# Pi_Zero_Radio_Alt_Hat.net
KiCad netlist of a schematic drawn in EasyEDA
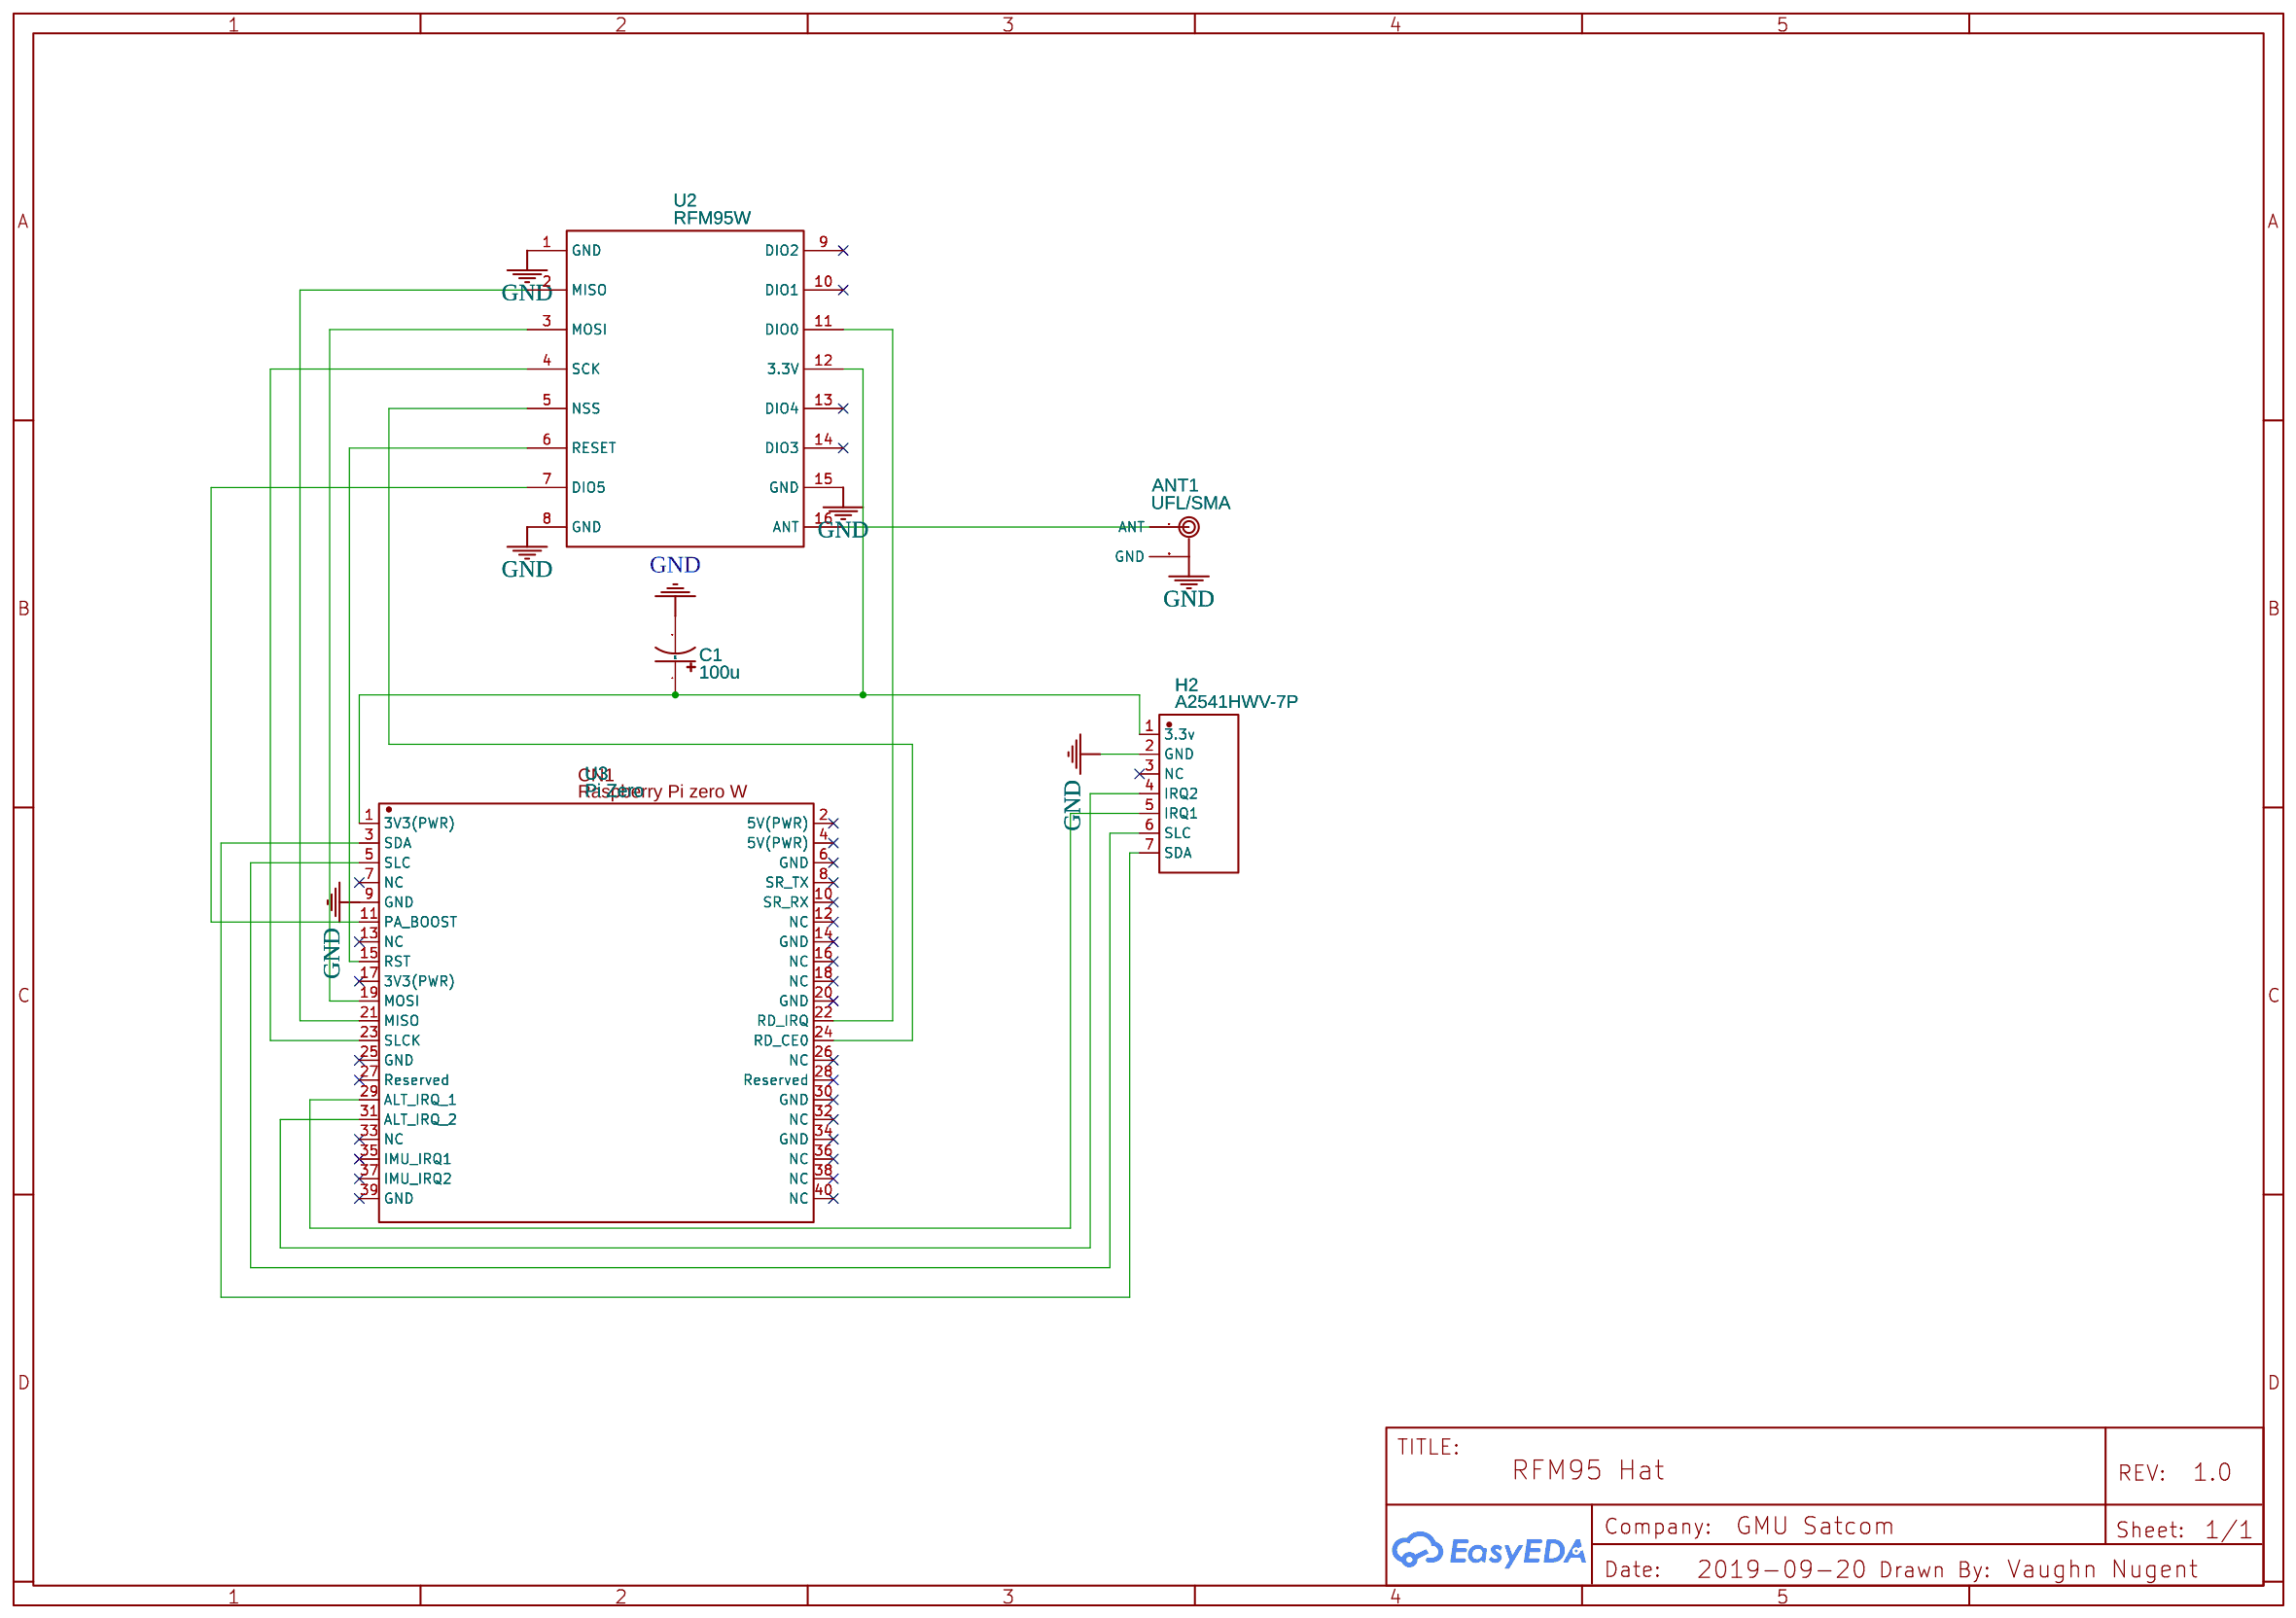
[diagram p0: schematic sheet]

(export (version "E")
  (design (tool "Eeschema 10.0.6"))
  (components
    (comp (ref "ANT1")
      (value "UFL/SMA")
      (fields (field (name "BOM_Manufacturer Part") "UFL/SMA anténa"))
      (libsource (lib "") (part "Unknown_595_275"))
    )
    (comp (ref "C1") (value "100u") (libsource (lib "") (part "Cap_Electrolytic(TH)_D3.0XF1.5_US")))
    (comp (ref "H2")
      (value "A2541HWV-7P")
      (fields (field (name "BOM_Supplier Part") "C225504"))
      (libsource (lib "") (part "Unknown_595_395"))
    )
    (comp (ref "U2") (value "RFM95W") (libsource (lib "") (part "Unknown_340_190")))
    (comp (ref "U3") (value "Pi Zero") (libsource (lib "") (part "Unknown_295_495")))
  )
  (nets
    (net (code "1") (name "GND") (class "Default")
      (node (ref "ANT1") (pin "GND") (pinfunction "GND_GND") (pintype "unspecified"))
      (node (ref "C1") (pin "2") (pinfunction "Neg_2") (pintype "unspecified"))
      (node (ref "H2") (pin "2") (pinfunction "GND_2") (pintype "unspecified"))
      (node (ref "U2") (pin "1") (pinfunction "GND_1") (pintype "unspecified"))
      (node (ref "U2") (pin "15") (pinfunction "GND_15") (pintype "unspecified"))
      (node (ref "U2") (pin "8") (pinfunction "GND_8") (pintype "unspecified"))
      (node (ref "U3") (pin "9") (pinfunction "GND_9") (pintype "passive"))
    )
    (net (code "2") (name "Net-(C1-Pos)") (class "Default")
      (node (ref "C1") (pin "1") (pinfunction "Pos_1") (pintype "unspecified"))
      (node (ref "H2") (pin "1") (pinfunction "3.3v_1") (pintype "unspecified"))
      (node (ref "U2") (pin "12") (pinfunction "3.3V_12") (pintype "unspecified"))
      (node (ref "U3") (pin "1") (pinfunction "3V3(PWR)_1") (pintype "passive"))
    )
    (net (code "3") (name "Net-(H2-IRQ1)") (class "Default")
      (node (ref "H2") (pin "5") (pinfunction "IRQ1_5") (pintype "unspecified"))
      (node (ref "U3") (pin "29") (pinfunction "ALT_IRQ_1_29") (pintype "bidirectional"))
    )
    (net (code "4") (name "Net-(H2-IRQ2)") (class "Default")
      (node (ref "H2") (pin "4") (pinfunction "IRQ2_4") (pintype "unspecified"))
      (node (ref "U3") (pin "31") (pinfunction "ALT_IRQ_2_31") (pintype "bidirectional"))
    )
    (net (code "5") (name "Net-(H2-SDA)") (class "Default")
      (node (ref "H2") (pin "7") (pinfunction "SDA_7") (pintype "unspecified"))
      (node (ref "U3") (pin "3") (pinfunction "SDA_3") (pintype "bidirectional"))
    )
    (net (code "6") (name "Net-(H2-SLC)") (class "Default")
      (node (ref "H2") (pin "6") (pinfunction "SLC_6") (pintype "unspecified"))
      (node (ref "U3") (pin "5") (pinfunction "SLC_5") (pintype "bidirectional"))
    )
    (net (code "7") (name "Net-(U2-ANT)") (class "Default")
      (node (ref "ANT1") (pin "ANT") (pinfunction "ANT_ANT") (pintype "unspecified"))
      (node (ref "U2") (pin "16") (pinfunction "ANT_16") (pintype "unspecified"))
    )
    (net (code "8") (name "Net-(U2-DIO0)") (class "Default")
      (node (ref "U2") (pin "11") (pinfunction "DIO0_11") (pintype "unspecified"))
      (node (ref "U3") (pin "22") (pinfunction "RD_IRQ_22") (pintype "bidirectional"))
    )
    (net (code "9") (name "Net-(U2-DIO5)") (class "Default")
      (node (ref "U2") (pin "7") (pinfunction "DIO5_7") (pintype "unspecified"))
      (node (ref "U3") (pin "11") (pinfunction "PA_BOOST_11") (pintype "bidirectional"))
    )
    (net (code "10") (name "Net-(U2-MISO)") (class "Default")
      (node (ref "U2") (pin "2") (pinfunction "MISO_2") (pintype "unspecified"))
      (node (ref "U3") (pin "21") (pinfunction "MISO_21") (pintype "bidirectional"))
    )
    (net (code "11") (name "Net-(U2-MOSI)") (class "Default")
      (node (ref "U2") (pin "3") (pinfunction "MOSI_3") (pintype "unspecified"))
      (node (ref "U3") (pin "19") (pinfunction "MOSI_19") (pintype "bidirectional"))
    )
    (net (code "12") (name "Net-(U2-NSS)") (class "Default")
      (node (ref "U2") (pin "5") (pinfunction "NSS_5") (pintype "unspecified"))
      (node (ref "U3") (pin "24") (pinfunction "RD_CE0_24") (pintype "bidirectional"))
    )
    (net (code "13") (name "Net-(U2-RESET)") (class "Default")
      (node (ref "U2") (pin "6") (pinfunction "RESET_6") (pintype "unspecified"))
      (node (ref "U3") (pin "15") (pinfunction "RST_15") (pintype "output"))
    )
    (net (code "14") (name "Net-(U2-SCK)") (class "Default")
      (node (ref "U2") (pin "4") (pinfunction "SCK_4") (pintype "unspecified"))
      (node (ref "U3") (pin "23") (pinfunction "SLCK_23") (pintype "bidirectional"))
    )
    (net (code "15") (name "unconnected-(H2-NC-Pad3)") (class "Default")
      (node (ref "H2") (pin "3") (pinfunction "NC_3") (pintype "unspecified+no_connect"))
    )
    (net (code "16") (name "unconnected-(U2-DIO1-Pad10)") (class "Default")
      (node (ref "U2") (pin "10") (pinfunction "DIO1_10") (pintype "unspecified+no_connect"))
    )
    (net (code "17") (name "unconnected-(U2-DIO2-Pad9)") (class "Default")
      (node (ref "U2") (pin "9") (pinfunction "DIO2_9") (pintype "unspecified+no_connect"))
    )
    (net (code "18") (name "unconnected-(U2-DIO3-Pad14)") (class "Default")
      (node (ref "U2") (pin "14") (pinfunction "DIO3_14") (pintype "unspecified+no_connect"))
    )
    (net (code "19") (name "unconnected-(U2-DIO4-Pad13)") (class "Default")
      (node (ref "U2") (pin "13") (pinfunction "DIO4_13") (pintype "unspecified+no_connect"))
    )
    (net (code "20") (name "unconnected-(U3-3V3(PWR)-Pad17)") (class "Default")
      (node (ref "U3") (pin "17") (pinfunction "3V3(PWR)_17") (pintype "passive+no_connect"))
    )
    (net (code "21") (name "unconnected-(U3-5V(PWR)-Pad2)") (class "Default")
      (node (ref "U3") (pin "2") (pinfunction "5V(PWR)_2") (pintype "passive+no_connect"))
    )
    (net (code "22") (name "unconnected-(U3-5V(PWR)-Pad4)") (class "Default")
      (node (ref "U3") (pin "4") (pinfunction "5V(PWR)_4") (pintype "passive+no_connect"))
    )
    (net (code "23") (name "unconnected-(U3-GND-Pad6)") (class "Default")
      (node (ref "U3") (pin "6") (pinfunction "GND_6") (pintype "passive+no_connect"))
    )
    (net (code "24") (name "unconnected-(U3-GND-Pad14)") (class "Default")
      (node (ref "U3") (pin "14") (pinfunction "GND_14") (pintype "passive+no_connect"))
    )
    (net (code "25") (name "unconnected-(U3-GND-Pad20)") (class "Default")
      (node (ref "U3") (pin "20") (pinfunction "GND_20") (pintype "passive+no_connect"))
    )
    (net (code "26") (name "unconnected-(U3-GND-Pad25)") (class "Default")
      (node (ref "U3") (pin "25") (pinfunction "GND_25") (pintype "passive+no_connect"))
    )
    (net (code "27") (name "unconnected-(U3-GND-Pad30)") (class "Default")
      (node (ref "U3") (pin "30") (pinfunction "GND_30") (pintype "passive+no_connect"))
    )
    (net (code "28") (name "unconnected-(U3-GND-Pad34)") (class "Default")
      (node (ref "U3") (pin "34") (pinfunction "GND_34") (pintype "passive+no_connect"))
    )
    (net (code "29") (name "unconnected-(U3-GND-Pad39)") (class "Default")
      (node (ref "U3") (pin "39") (pinfunction "GND_39") (pintype "passive+no_connect"))
    )
    (net (code "30") (name "unconnected-(U3-IMU_IRQ1-Pad35)") (class "Default")
      (node (ref "U3") (pin "35") (pinfunction "IMU_IRQ1_35") (pintype "bidirectional+no_connect"))
    )
    (net (code "31") (name "unconnected-(U3-IMU_IRQ2-Pad37)") (class "Default")
      (node (ref "U3") (pin "37") (pinfunction "IMU_IRQ2_37") (pintype "bidirectional+no_connect"))
    )
    (net (code "32") (name "unconnected-(U3-NC-Pad7)") (class "Default")
      (node (ref "U3") (pin "7") (pinfunction "NC_7") (pintype "bidirectional+no_connect"))
    )
    (net (code "33") (name "unconnected-(U3-NC-Pad12)") (class "Default")
      (node (ref "U3") (pin "12") (pinfunction "NC_12") (pintype "bidirectional+no_connect"))
    )
    (net (code "34") (name "unconnected-(U3-NC-Pad13)") (class "Default")
      (node (ref "U3") (pin "13") (pinfunction "NC_13") (pintype "bidirectional+no_connect"))
    )
    (net (code "35") (name "unconnected-(U3-NC-Pad16)") (class "Default")
      (node (ref "U3") (pin "16") (pinfunction "NC_16") (pintype "bidirectional+no_connect"))
    )
    (net (code "36") (name "unconnected-(U3-NC-Pad18)") (class "Default")
      (node (ref "U3") (pin "18") (pinfunction "NC_18") (pintype "bidirectional+no_connect"))
    )
    (net (code "37") (name "unconnected-(U3-NC-Pad26)") (class "Default")
      (node (ref "U3") (pin "26") (pinfunction "NC_26") (pintype "bidirectional+no_connect"))
    )
    (net (code "38") (name "unconnected-(U3-NC-Pad32)") (class "Default")
      (node (ref "U3") (pin "32") (pinfunction "NC_32") (pintype "bidirectional+no_connect"))
    )
    (net (code "39") (name "unconnected-(U3-NC-Pad33)") (class "Default")
      (node (ref "U3") (pin "33") (pinfunction "NC_33") (pintype "bidirectional+no_connect"))
    )
    (net (code "40") (name "unconnected-(U3-NC-Pad36)") (class "Default")
      (node (ref "U3") (pin "36") (pinfunction "NC_36") (pintype "bidirectional+no_connect"))
    )
    (net (code "41") (name "unconnected-(U3-NC-Pad38)") (class "Default")
      (node (ref "U3") (pin "38") (pinfunction "NC_38") (pintype "bidirectional+no_connect"))
    )
    (net (code "42") (name "unconnected-(U3-NC-Pad40)") (class "Default")
      (node (ref "U3") (pin "40") (pinfunction "NC_40") (pintype "bidirectional+no_connect"))
    )
    (net (code "43") (name "unconnected-(U3-Reserved-Pad27)") (class "Default")
      (node (ref "U3") (pin "27") (pinfunction "Reserved_27") (pintype "unspecified+no_connect"))
    )
    (net (code "44") (name "unconnected-(U3-Reserved-Pad28)") (class "Default")
      (node (ref "U3") (pin "28") (pinfunction "Reserved_28") (pintype "unspecified+no_connect"))
    )
    (net (code "45") (name "unconnected-(U3-SR_RX-Pad10)") (class "Default")
      (node (ref "U3") (pin "10") (pinfunction "SR_RX_10") (pintype "bidirectional+no_connect"))
    )
    (net (code "46") (name "unconnected-(U3-SR_TX-Pad8)") (class "Default")
      (node (ref "U3") (pin "8") (pinfunction "SR_TX_8") (pintype "passive+no_connect"))
    )
  )
)
